# UU-PCBA-MANT_Top.net
KiCad netlist of a schematic drawn in Altium Designer
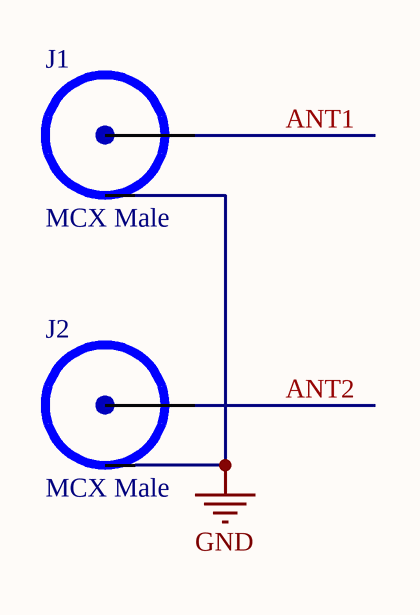
[diagram p0: UU-PCBA-MANT_Top.SchDoc]

(export (version "E")
  (design (tool "Eeschema 10.0.6"))
  (components
    (comp (ref "J1")
      (value "MCX Male")
      (footprint "RSP-199156-01")
      (description "Samtec MODIFIED 50 OHM MCX JACK PLUG, THROUGH-HOLE")
      (libsource (lib "open_src_utah") (part "RSP-199156-01"))
    )
    (comp (ref "J2")
      (value "MCX Male")
      (footprint "RSP-199156-01")
      (description "Samtec MODIFIED 50 OHM MCX JACK PLUG, THROUGH-HOLE")
      (libsource (lib "open_src_utah") (part "RSP-199156-01"))
    )
  )
  (nets
    (net (code "1") (name "/ANT1") (class "Default")
      (node (ref "J1") (pin "1") (pinfunction "SIG_1") (pintype "power_in"))
    )
    (net (code "2") (name "/ANT2") (class "Default")
      (node (ref "J2") (pin "1") (pinfunction "SIG_1") (pintype "power_in"))
    )
    (net (code "3") (name "GND") (class "Default")
      (node (ref "J1") (pin "0") (pinfunction "GND_0") (pintype "power_in"))
      (node (ref "J2") (pin "0") (pinfunction "GND_0") (pintype "power_in"))
    )
  )
)
